# Yusynth_VCA.net
KiCad netlist of a schematic drawn in Altium Designer
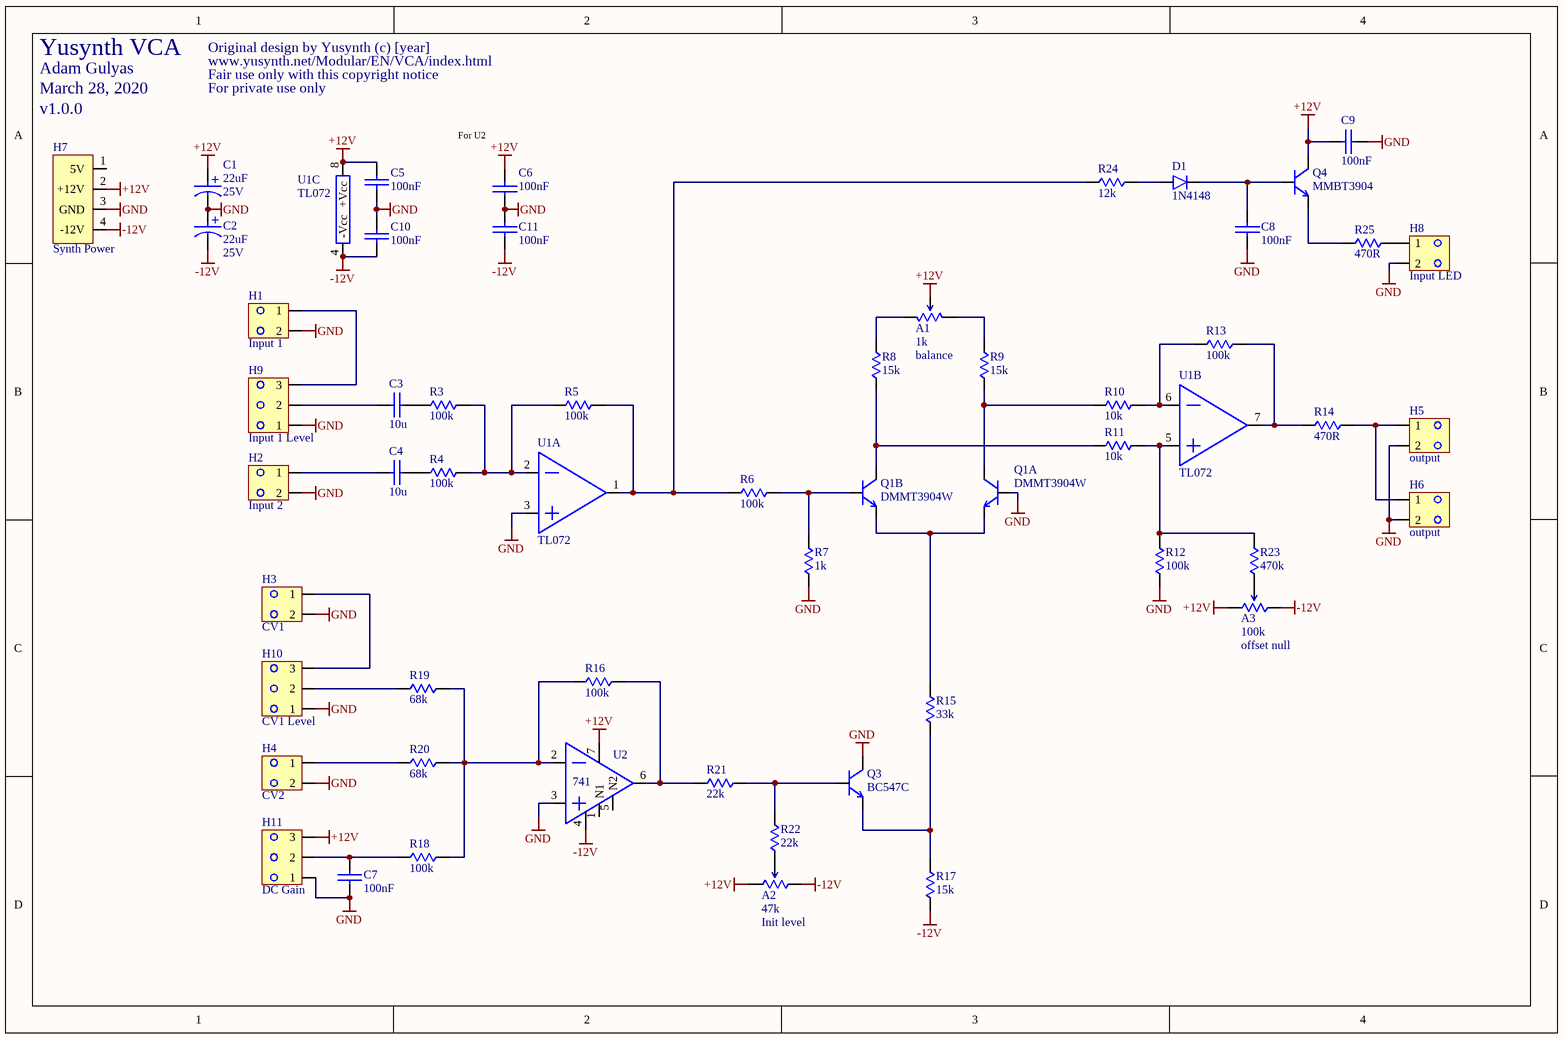
[diagram p0: Yusynth VCA.SchDoc]

(export (version "E")
  (design (tool "Eeschema 10.0.6"))
  (components
    (comp (ref "A1")
      (value "1k")
      (footprint "trim pot")
      (description "trim pot from the random eBay set")
      (fields (field (name "MFG") "Unknown") (field (name "PURPOSE") "balance"))
      (libsource (lib "Adam home") (part "pot - trim - random eBay"))
    )
    (comp (ref "A2")
      (value "47k")
      (footprint "trim pot")
      (description "trim pot from the random eBay set")
      (fields (field (name "MFG") "Unknown") (field (name "PURPOSE") "Init level"))
      (libsource (lib "Adam home") (part "pot - trim - random eBay"))
    )
    (comp (ref "A3")
      (value "100k")
      (footprint "trim pot")
      (description "trim pot from the random eBay set")
      (fields (field (name "MFG") "Unknown") (field (name "PURPOSE") "offset null"))
      (libsource (lib "Adam home") (part "pot - trim - random eBay"))
    )
    (comp (ref "C1")
      (value "22uF")
      (footprint "C - Wurth - SMT - 5mm Dia can")
      (description "CAP 22 UF 20% 25 V")
      (fields
        (field (name "MFG") "Wurth Electronics Inc.")
        (field (name "TOLERANCE") "±20%")
        (field (name "VOLTAGE") "25V")
      )
      (libsource (lib "Adam home") (part "c - 22uF 25V Alum SMT"))
    )
    (comp (ref "C2")
      (value "22uF")
      (footprint "C - Wurth - SMT - 5mm Dia can")
      (description "CAP 22 UF 20% 25 V")
      (fields
        (field (name "MFG") "Wurth Electronics Inc.")
        (field (name "TOLERANCE") "±20%")
        (field (name "VOLTAGE") "25V")
      )
      (libsource (lib "Adam home") (part "c - 22uF 25V Alum SMT"))
    )
    (comp (ref "C3")
      (value "10u")
      (footprint "JEDEC - 0805")
      (description "CAP CER 10UF 35V X5R 0805")
      (fields (field (name "MFG") "Murata") (field (name "VOLTAGE") "35V"))
      (libsource (lib "Adam home") (part "c - 10uF 35V 0805"))
    )
    (comp (ref "C4")
      (value "10u")
      (footprint "JEDEC - 0805")
      (description "CAP CER 10UF 35V X5R 0805")
      (fields (field (name "MFG") "Murata") (field (name "VOLTAGE") "35V"))
      (libsource (lib "Adam home") (part "c - 10uF 35V 0805"))
    )
    (comp (ref "C5")
      (value "100nF")
      (footprint "JEDEC - 0603")
      (description "CAP CER 0.1UF 50V X7R 0603")
      (fields (field (name "MFG") "Yageo") (field (name "VOLTAGE") "50V"))
      (libsource (lib "Adam home") (part "c - 100nF"))
    )
    (comp (ref "C6")
      (value "100nF")
      (footprint "JEDEC - 0603")
      (description "CAP CER 0.1UF 50V X7R 0603")
      (fields (field (name "MFG") "Yageo") (field (name "VOLTAGE") "50V"))
      (libsource (lib "Adam home") (part "c - 100nF"))
    )
    (comp (ref "C7")
      (value "100nF")
      (footprint "JEDEC - 0603")
      (description "CAP CER 0.1UF 50V X7R 0603")
      (fields (field (name "MFG") "Yageo") (field (name "VOLTAGE") "50V"))
      (libsource (lib "Adam home") (part "c - 100nF"))
    )
    (comp (ref "C8")
      (value "100nF")
      (footprint "JEDEC - 0603")
      (description "CAP CER 0.1UF 50V X7R 0603")
      (fields (field (name "MFG") "Yageo") (field (name "VOLTAGE") "50V"))
      (libsource (lib "Adam home") (part "c - 100nF"))
    )
    (comp (ref "C9")
      (value "100nF")
      (footprint "JEDEC - 0603")
      (description "CAP CER 0.1UF 50V X7R 0603")
      (fields (field (name "MFG") "Yageo") (field (name "VOLTAGE") "50V"))
      (libsource (lib "Adam home") (part "c - 100nF"))
    )
    (comp (ref "C10")
      (value "100nF")
      (footprint "JEDEC - 0603")
      (description "CAP CER 0.1UF 50V X7R 0603")
      (fields (field (name "MFG") "Yageo") (field (name "VOLTAGE") "50V"))
      (libsource (lib "Adam home") (part "c - 100nF"))
    )
    (comp (ref "C11")
      (value "100nF")
      (footprint "JEDEC - 0603")
      (description "CAP CER 0.1UF 50V X7R 0603")
      (fields (field (name "MFG") "Yageo") (field (name "VOLTAGE") "50V"))
      (libsource (lib "Adam home") (part "c - 100nF"))
    )
    (comp (ref "D1")
      (value "1N4148")
      (footprint "SOD 123")
      (description "DIODE GEN PURP 75V 250MA SOD123")
      (fields (field (name "MFG") "SMC Diode Solutions"))
      (libsource (lib "Adam home") (part "Diode - 1N4148 - SOD123"))
    )
    (comp (ref "H1")
      (value "1x2 TH Male")
      (footprint "H - KK 100 - TH - 1x2")
      (description "CONN HEADER 2POS .100 VERT TIN")
      (fields (field (name "MFG") "Molex") (field (name "PURPOSE") "Input 1"))
      (libsource (lib "") (part "Header - KK 6373 - 1x2_1"))
    )
    (comp (ref "H2")
      (value "1x2 TH Male")
      (footprint "H - KK 100 - TH - 1x2")
      (description "CONN HEADER 2POS .100 VERT TIN")
      (fields (field (name "MFG") "Molex") (field (name "PURPOSE") "Input 2"))
      (libsource (lib "") (part "Header - KK 6373 - 1x2_1"))
    )
    (comp (ref "H3")
      (value "1x2 TH Male")
      (footprint "H - KK 100 - TH - 1x2")
      (description "CONN HEADER 2POS .100 VERT TIN")
      (fields (field (name "MFG") "Molex") (field (name "PURPOSE") "CV1"))
      (libsource (lib "") (part "Header - KK 6373 - 1x2_1"))
    )
    (comp (ref "H4")
      (value "1x2 TH Male")
      (footprint "H - KK 100 - TH - 1x2")
      (description "CONN HEADER 2POS .100 VERT TIN")
      (fields (field (name "MFG") "Molex") (field (name "PURPOSE") "CV2"))
      (libsource (lib "") (part "Header - KK 6373 - 1x2_1"))
    )
    (comp (ref "H5")
      (value "1x2 TH Male")
      (footprint "H - KK 100 - TH - 1x2")
      (description "CONN HEADER 2POS .100 VERT TIN")
      (fields (field (name "MFG") "Molex") (field (name "PURPOSE") "output"))
      (libsource (lib "Adam home") (part "Header - KK 6373 - 1x2"))
    )
    (comp (ref "H6")
      (value "1x2 TH Male")
      (footprint "H - KK 100 - TH - 1x2")
      (description "CONN HEADER 2POS .100 VERT TIN")
      (fields (field (name "MFG") "Molex") (field (name "PURPOSE") "output"))
      (libsource (lib "Adam home") (part "Header - KK 6373 - 1x2"))
    )
    (comp (ref "H7")
      (value "Synth Power")
      (footprint "Power Connector 3")
      (description "CONN HEADER EH SIDE 6POS 2.5MM")
      (fields (field (name "MFG") "S6B-EH(LF)(SN)"))
      (libsource (lib "Synth UI") (part "h - Power - 1x4"))
    )
    (comp (ref "H8")
      (value "1x2 TH Male")
      (footprint "H - KK 100 - TH - 1x2")
      (description "CONN HEADER 2POS .100 VERT TIN")
      (fields (field (name "MFG") "Molex") (field (name "PURPOSE") "Input LED"))
      (libsource (lib "Adam home") (part "Header - KK 6373 - 1x2"))
    )
    (comp (ref "H9")
      (value "1x3 TH Male")
      (footprint "H - KK 100 - TH - 1x3")
      (description "CONN HEADER 3POS .100 VERT TIN")
      (fields (field (name "MFG") "Molex") (field (name "PURPOSE") "Input 1 Level"))
      (libsource (lib "Adam home") (part "Header - KK 6373 - 1x3"))
    )
    (comp (ref "H10")
      (value "1x3 TH Male")
      (footprint "H - KK 100 - TH - 1x3")
      (description "CONN HEADER 3POS .100 VERT TIN")
      (fields (field (name "MFG") "Molex") (field (name "PURPOSE") "CV1 Level"))
      (libsource (lib "Adam home") (part "Header - KK 6373 - 1x3"))
    )
    (comp (ref "H11")
      (value "1x3 TH Male")
      (footprint "H - KK 100 - TH - 1x3")
      (description "CONN HEADER 3POS .100 VERT TIN")
      (fields (field (name "MFG") "Molex") (field (name "PURPOSE") "DC Gain"))
      (libsource (lib "Adam home") (part "Header - KK 6373 - 1x3"))
    )
    (comp (ref "Q1")
      (value "DMMT3904W")
      (footprint "Diodes Inc - SOT363")
      (description "TRANS 2NPN 40V 0.2A SOT363")
      (fields (field (name "MFG") "Diodes Inc."))
      (libsource (lib "Adam home") (part "tran - matched npn - DMMT3904W"))
    )
    (comp (ref "Q3")
      (value "BC547C")
      (footprint "TO 92 - ON Semi")
      (description "TRANS NPN 45V 0.1A TO-92")
      (fields (field (name "MFG") "ON Semi"))
      (libsource (lib "Adam home") (part "t - BJT - npn - BC547C"))
    )
    (comp (ref "Q4")
      (value "MMBT3904")
      (footprint "SOT 23")
      (description "TRANS NPN 40V 0.2A SOT23")
      (fields (field (name "MFG") "ON Semi"))
      (libsource (lib "Adam home") (part "t - BJT - npn - MMBT3904"))
    )
    (comp (ref "R3")
      (value "100k")
      (footprint "JEDEC - 0603")
      (description "RES SMD 100K OHM 5% 1/10W 0603")
      (fields (field (name "MFG") "Yageo") (field (name "POWER") "0.1W"))
      (libsource (lib "stock R") (part "5 - 100K 5% 0603"))
    )
    (comp (ref "R4")
      (value "100k")
      (footprint "JEDEC - 0603")
      (description "RES SMD 100K OHM 5% 1/10W 0603")
      (fields (field (name "MFG") "Yageo") (field (name "POWER") "0.1W"))
      (libsource (lib "stock R") (part "5 - 100K 5% 0603"))
    )
    (comp (ref "R5")
      (value "100k")
      (footprint "JEDEC - 0603")
      (description "RES SMD 100K OHM 5% 1/10W 0603")
      (fields (field (name "MFG") "Yageo") (field (name "POWER") "0.1W"))
      (libsource (lib "stock R") (part "5 - 100K 5% 0603"))
    )
    (comp (ref "R6")
      (value "100k")
      (footprint "JEDEC - 0603")
      (description "RES SMD 100K OHM 5% 1/10W 0603")
      (fields (field (name "MFG") "Yageo") (field (name "POWER") "0.1W"))
      (libsource (lib "stock R") (part "5 - 100K 5% 0603"))
    )
    (comp (ref "R7")
      (value "1k")
      (footprint "JEDEC - 0603")
      (description "RES SMD 1K OHM 5% 1/10W 0603")
      (fields (field (name "MFG") "Yageo") (field (name "POWER") "0.1W"))
      (libsource (lib "stock R") (part "3 - 1.0K 5% 0603"))
    )
    (comp (ref "R8")
      (value "15k")
      (footprint "JEDEC - 0603")
      (description "RES SMD 15K OHM 5% 1/10W 0603")
      (fields (field (name "MFG") "Yageo") (field (name "POWER") "0.1W"))
      (libsource (lib "stock R") (part "4 - 15K 5% 0603"))
    )
    (comp (ref "R9")
      (value "15k")
      (footprint "JEDEC - 0603")
      (description "RES SMD 15K OHM 5% 1/10W 0603")
      (fields (field (name "MFG") "Yageo") (field (name "POWER") "0.1W"))
      (libsource (lib "stock R") (part "4 - 15K 5% 0603"))
    )
    (comp (ref "R10")
      (value "10k")
      (footprint "JEDEC - 0603")
      (description "RES SMD 10K OHM 5% 1/10W 0603")
      (fields (field (name "MFG") "Yageo") (field (name "POWER") "0.1W"))
      (libsource (lib "stock R") (part "4 - 10K 5% 0603"))
    )
    (comp (ref "R11")
      (value "10k")
      (footprint "JEDEC - 0603")
      (description "RES SMD 10K OHM 5% 1/10W 0603")
      (fields (field (name "MFG") "Yageo") (field (name "POWER") "0.1W"))
      (libsource (lib "stock R") (part "4 - 10K 5% 0603"))
    )
    (comp (ref "R12")
      (value "100k")
      (footprint "JEDEC - 0603")
      (description "RES SMD 100K OHM 5% 1/10W 0603")
      (fields (field (name "MFG") "Yageo") (field (name "POWER") "0.1W"))
      (libsource (lib "stock R") (part "5 - 100K 5% 0603"))
    )
    (comp (ref "R13")
      (value "100k")
      (footprint "JEDEC - 0603")
      (description "RES SMD 100K OHM 5% 1/10W 0603")
      (fields (field (name "MFG") "Yageo") (field (name "POWER") "0.1W"))
      (libsource (lib "stock R") (part "5 - 100K 5% 0603"))
    )
    (comp (ref "R14")
      (value "470R")
      (footprint "JEDEC - 0603")
      (description "RES SMD 470 OHM 5% 1/10W 0603")
      (fields (field (name "MFG") "Yageo") (field (name "POWER") "0.1W"))
      (libsource (lib "stock R") (part "2 - 470R 5% 0603"))
    )
    (comp (ref "R15")
      (value "33k")
      (footprint "JEDEC - 0603")
      (description "RES SMD 33K OHM 5% 1/10W 0603")
      (fields (field (name "MFG") "Yageo") (field (name "POWER") "0.1W"))
      (libsource (lib "stock R") (part "4 - 33K 5% 0603"))
    )
    (comp (ref "R16")
      (value "100k")
      (footprint "JEDEC - 0603")
      (description "RES SMD 100K OHM 5% 1/10W 0603")
      (fields (field (name "MFG") "Yageo") (field (name "POWER") "0.1W"))
      (libsource (lib "stock R") (part "5 - 100K 5% 0603"))
    )
    (comp (ref "R17")
      (value "15k")
      (footprint "JEDEC - 0603")
      (description "RES SMD 15K OHM 5% 1/10W 0603")
      (fields (field (name "MFG") "Yageo") (field (name "POWER") "0.1W"))
      (libsource (lib "stock R") (part "4 - 15K 5% 0603"))
    )
    (comp (ref "R18")
      (value "100k")
      (footprint "JEDEC - 0603")
      (description "RES SMD 100K OHM 5% 1/10W 0603")
      (fields (field (name "MFG") "Yageo") (field (name "POWER") "0.1W"))
      (libsource (lib "stock R") (part "5 - 100K 5% 0603"))
    )
    (comp (ref "R19")
      (value "68k")
      (footprint "JEDEC - 0603")
      (description "RES SMD 68K OHM 5% 1/10W 0603")
      (fields (field (name "MFG") "Yageo") (field (name "POWER") "0.1W"))
      (libsource (lib "stock R") (part "4 - 68K 5% 0603"))
    )
    (comp (ref "R20")
      (value "68k")
      (footprint "JEDEC - 0603")
      (description "RES SMD 68K OHM 5% 1/10W 0603")
      (fields (field (name "MFG") "Yageo") (field (name "POWER") "0.1W"))
      (libsource (lib "stock R") (part "4 - 68K 5% 0603"))
    )
    (comp (ref "R21")
      (value "22k")
      (footprint "JEDEC - 0603")
      (description "RES SMD 22K OHM 5% 1/10W 0603")
      (fields (field (name "MFG") "Yageo") (field (name "POWER") "0.1W"))
      (libsource (lib "stock R") (part "4 - 22K 5% 0603"))
    )
    (comp (ref "R22")
      (value "22k")
      (footprint "JEDEC - 0603")
      (description "RES SMD 22K OHM 5% 1/10W 0603")
      (fields (field (name "MFG") "Yageo") (field (name "POWER") "0.1W"))
      (libsource (lib "stock R") (part "4 - 22K 5% 0603"))
    )
    (comp (ref "R23")
      (value "470k")
      (footprint "JEDEC - 0603")
      (description "RES SMD 470K OHM 5% 1/10W 0603")
      (fields (field (name "MFG") "Yageo") (field (name "POWER") "0.1W"))
      (libsource (lib "stock R") (part "5 - 470K 5% 0603"))
    )
    (comp (ref "R24")
      (value "12k")
      (footprint "JEDEC - 0603")
      (description "RES SMD 12K OHM 5% 1/10W 0603")
      (fields (field (name "MFG") "Yageo") (field (name "POWER") "0.1W"))
      (libsource (lib "stock R") (part "4 - 12K 5% 0603"))
    )
    (comp (ref "R25")
      (value "470R")
      (footprint "JEDEC - 0603")
      (description "RES SMD 470 OHM 5% 1/10W 0603")
      (fields (field (name "MFG") "Yageo") (field (name "POWER") "0.1W"))
      (libsource (lib "stock R") (part "2 - 470R 5% 0603"))
    )
    (comp (ref "U1")
      (value "TL072")
      (footprint "TI - D (R-PDSO-G8)")
      (description "IC OPAMP JFET 3MHZ 8SOIC")
      (fields (field (name "MFG") "TI"))
      (libsource (lib "Adam home") (part "op amp - TL072"))
    )
    (comp (ref "U2")
      (value "741")
      (footprint "TI - D (R-PDSO-G8)")
      (description "IC OPAMP GP 1MHZ 8SOIC")
      (fields (field (name "MFG") "TI"))
      (libsource (lib "Adam home") (part "op amp - UA741 - TI UA741CDR"))
    )
  )
  (nets
    (net (code "1") (name "+12V") (class "Default")
      (node (ref "A1") (pin "2") (pinfunction "2_2") (pintype "passive"))
      (node (ref "A2") (pin "3") (pinfunction "3_3") (pintype "passive"))
      (node (ref "A3") (pin "3") (pinfunction "3_3") (pintype "passive"))
      (node (ref "C1") (pin "1") (pinfunction "1_1") (pintype "passive"))
      (node (ref "C5") (pin "2") (pintype "passive"))
      (node (ref "C6") (pin "2") (pintype "passive"))
      (node (ref "C9") (pin "1") (pintype "passive"))
      (node (ref "H11") (pin "3") (pinfunction "3_3") (pintype "passive"))
      (node (ref "H7") (pin "2") (pinfunction "+12V_2") (pintype "passive"))
      (node (ref "Q4") (pin "3") (pinfunction "C_3") (pintype "passive"))
      (node (ref "U1") (pin "8") (pinfunction "+Vcc_8") (pintype "passive"))
      (node (ref "U2") (pin "7") (pinfunction "7_7") (pintype "passive"))
    )
    (net (code "2") (name "-12V") (class "Default")
      (node (ref "A2") (pin "1") (pintype "passive"))
      (node (ref "A3") (pin "1") (pintype "passive"))
      (node (ref "C10") (pin "1") (pintype "passive"))
      (node (ref "C11") (pin "1") (pintype "passive"))
      (node (ref "C2") (pin "2") (pinfunction "2_2") (pintype "passive"))
      (node (ref "H7") (pin "4") (pinfunction "-12V_4") (pintype "passive"))
      (node (ref "R17") (pin "1") (pintype "passive"))
      (node (ref "U1") (pin "4") (pinfunction "-Vcc_4") (pintype "passive"))
      (node (ref "U2") (pin "4") (pinfunction "4_4") (pintype "passive"))
    )
    (net (code "3") (name "GND") (class "Default")
      (node (ref "C1") (pin "2") (pinfunction "2_2") (pintype "passive"))
      (node (ref "C10") (pin "2") (pintype "passive"))
      (node (ref "C11") (pin "2") (pintype "passive"))
      (node (ref "C2") (pin "1") (pinfunction "1_1") (pintype "passive"))
      (node (ref "C5") (pin "1") (pintype "passive"))
      (node (ref "C6") (pin "1") (pintype "passive"))
      (node (ref "C7") (pin "1") (pintype "passive"))
      (node (ref "C8") (pin "2") (pintype "passive"))
      (node (ref "C9") (pin "2") (pintype "passive"))
      (node (ref "H1") (pin "2") (pinfunction "2_2") (pintype "passive"))
      (node (ref "H10") (pin "1") (pinfunction "1_1") (pintype "passive"))
      (node (ref "H11") (pin "1") (pinfunction "1_1") (pintype "passive"))
      (node (ref "H2") (pin "2") (pinfunction "2_2") (pintype "passive"))
      (node (ref "H3") (pin "2") (pinfunction "2_2") (pintype "passive"))
      (node (ref "H4") (pin "2") (pinfunction "2_2") (pintype "passive"))
      (node (ref "H5") (pin "2") (pinfunction "2_2") (pintype "passive"))
      (node (ref "H6") (pin "2") (pinfunction "2_2") (pintype "passive"))
      (node (ref "H7") (pin "3") (pinfunction "GND_3") (pintype "passive"))
      (node (ref "H8") (pin "2") (pinfunction "2_2") (pintype "passive"))
      (node (ref "H9") (pin "1") (pinfunction "1_1") (pintype "passive"))
      (node (ref "Q1") (pin "1") (pinfunction "1_1") (pintype "passive"))
      (node (ref "Q3") (pin "1") (pinfunction "C_1") (pintype "passive"))
      (node (ref "R12") (pin "1") (pintype "passive"))
      (node (ref "R7") (pin "1") (pintype "passive"))
      (node (ref "U1") (pin "3") (pinfunction "3_3") (pintype "passive"))
      (node (ref "U2") (pin "3") (pinfunction "3_3") (pintype "passive"))
    )
    (net (code "4") (name "Net-(A1-Pad1)") (class "Default")
      (node (ref "A1") (pin "1") (pintype "passive"))
      (node (ref "R8") (pin "2") (pintype "passive"))
    )
    (net (code "5") (name "Net-(A1-Pad3)") (class "Default")
      (node (ref "A1") (pin "3") (pinfunction "3_3") (pintype "passive"))
      (node (ref "R9") (pin "2") (pintype "passive"))
    )
    (net (code "6") (name "Net-(A2-Pad2)") (class "Default")
      (node (ref "A2") (pin "2") (pinfunction "2_2") (pintype "passive"))
      (node (ref "R22") (pin "1") (pintype "passive"))
    )
    (net (code "7") (name "Net-(A3-Pad2)") (class "Default")
      (node (ref "A3") (pin "2") (pinfunction "2_2") (pintype "passive"))
      (node (ref "R23") (pin "1") (pintype "passive"))
    )
    (net (code "8") (name "Net-(C3-Pad1)") (class "Default")
      (node (ref "C3") (pin "1") (pintype "passive"))
      (node (ref "H9") (pin "2") (pinfunction "2_2") (pintype "passive"))
    )
    (net (code "9") (name "Net-(C3-Pad2)") (class "Default")
      (node (ref "C3") (pin "2") (pintype "passive"))
      (node (ref "R3") (pin "1") (pintype "passive"))
    )
    (net (code "10") (name "Net-(C4-Pad1)") (class "Default")
      (node (ref "C4") (pin "1") (pintype "passive"))
      (node (ref "H2") (pin "1") (pinfunction "1_1") (pintype "passive"))
    )
    (net (code "11") (name "Net-(C4-Pad2)") (class "Default")
      (node (ref "C4") (pin "2") (pintype "passive"))
      (node (ref "R4") (pin "1") (pintype "passive"))
    )
    (net (code "12") (name "Net-(C7-Pad2)") (class "Default")
      (node (ref "C7") (pin "2") (pintype "passive"))
      (node (ref "H11") (pin "2") (pinfunction "2_2") (pintype "passive"))
      (node (ref "R18") (pin "1") (pintype "passive"))
    )
    (net (code "13") (name "Net-(D1-Pad1)") (class "Default")
      (node (ref "D1") (pin "1") (pinfunction "1_1") (pintype "passive"))
      (node (ref "R24") (pin "2") (pintype "passive"))
    )
    (net (code "14") (name "Net-(H1-Pad1)") (class "Default")
      (node (ref "H1") (pin "1") (pinfunction "1_1") (pintype "passive"))
      (node (ref "H9") (pin "3") (pinfunction "3_3") (pintype "passive"))
    )
    (net (code "15") (name "Net-(H4-Pad1)") (class "Default")
      (node (ref "H4") (pin "1") (pinfunction "1_1") (pintype "passive"))
      (node (ref "R20") (pin "1") (pintype "passive"))
    )
    (net (code "16") (name "Net-(H5-Pad1)") (class "Default")
      (node (ref "H5") (pin "1") (pinfunction "1_1") (pintype "passive"))
      (node (ref "H6") (pin "1") (pinfunction "1_1") (pintype "passive"))
      (node (ref "R14") (pin "2") (pintype "passive"))
    )
    (net (code "17") (name "Net-(H8-Pad1)") (class "Default")
      (node (ref "H8") (pin "1") (pinfunction "1_1") (pintype "passive"))
      (node (ref "R25") (pin "2") (pintype "passive"))
    )
    (net (code "18") (name "Net-(H10-Pad2)") (class "Default")
      (node (ref "H10") (pin "2") (pinfunction "2_2") (pintype "passive"))
      (node (ref "R19") (pin "1") (pintype "passive"))
    )
    (net (code "19") (name "Net-(H10-Pad3)") (class "Default")
      (node (ref "H10") (pin "3") (pinfunction "3_3") (pintype "passive"))
      (node (ref "H3") (pin "1") (pinfunction "1_1") (pintype "passive"))
    )
    (net (code "20") (name "Net-(Q1-Pad2)") (class "Default")
      (node (ref "Q1") (pin "2") (pinfunction "2_2") (pintype "passive"))
      (node (ref "R6") (pin "2") (pintype "passive"))
      (node (ref "R7") (pin "2") (pintype "passive"))
    )
    (net (code "21") (name "Net-(Q1-Pad3)") (class "Default")
      (node (ref "Q1") (pin "3") (pinfunction "3_3") (pintype "passive"))
      (node (ref "R11") (pin "1") (pintype "passive"))
      (node (ref "R8") (pin "1") (pintype "passive"))
    )
    (net (code "22") (name "Net-(Q1-Pad4)") (class "Default")
      (node (ref "Q1") (pin "4") (pinfunction "4_4") (pintype "passive"))
      (node (ref "Q1") (pin "5") (pinfunction "5_5") (pintype "passive"))
      (node (ref "R15") (pin "2") (pintype "passive"))
    )
    (net (code "23") (name "Net-(Q1-Pad6)") (class "Default")
      (node (ref "Q1") (pin "6") (pinfunction "6_6") (pintype "passive"))
      (node (ref "R10") (pin "1") (pintype "passive"))
      (node (ref "R9") (pin "1") (pintype "passive"))
    )
    (net (code "24") (name "Net-(Q3-B)") (class "Default")
      (node (ref "Q3") (pin "2") (pinfunction "B_2") (pintype "passive"))
      (node (ref "R21") (pin "2") (pintype "passive"))
      (node (ref "R22") (pin "2") (pintype "passive"))
    )
    (net (code "25") (name "Net-(Q3-E)") (class "Default")
      (node (ref "Q3") (pin "3") (pinfunction "E_3") (pintype "passive"))
      (node (ref "R15") (pin "1") (pintype "passive"))
      (node (ref "R17") (pin "2") (pintype "passive"))
    )
    (net (code "26") (name "Net-(Q4-B)") (class "Default")
      (node (ref "C8") (pin "1") (pintype "passive"))
      (node (ref "D1") (pin "2") (pinfunction "2_2") (pintype "passive"))
      (node (ref "Q4") (pin "1") (pinfunction "B_1") (pintype "passive"))
    )
    (net (code "27") (name "Net-(Q4-E)") (class "Default")
      (node (ref "Q4") (pin "2") (pinfunction "E_2") (pintype "passive"))
      (node (ref "R25") (pin "1") (pintype "passive"))
    )
    (net (code "28") (name "Net-(R3-Pad2)") (class "Default")
      (node (ref "R3") (pin "2") (pintype "passive"))
      (node (ref "R4") (pin "2") (pintype "passive"))
      (node (ref "R5") (pin "1") (pintype "passive"))
      (node (ref "U1") (pin "2") (pinfunction "2_2") (pintype "passive"))
    )
    (net (code "29") (name "Net-(R10-Pad2)") (class "Default")
      (node (ref "R10") (pin "2") (pintype "passive"))
      (node (ref "R13") (pin "1") (pintype "passive"))
      (node (ref "U1") (pin "6") (pinfunction "6_6") (pintype "passive"))
    )
    (net (code "30") (name "Net-(R11-Pad2)") (class "Default")
      (node (ref "R11") (pin "2") (pintype "passive"))
      (node (ref "R12") (pin "2") (pintype "passive"))
      (node (ref "R23") (pin "2") (pintype "passive"))
      (node (ref "U1") (pin "5") (pinfunction "5_5") (pintype "passive"))
    )
    (net (code "31") (name "Net-(R13-Pad2)") (class "Default")
      (node (ref "R13") (pin "2") (pintype "passive"))
      (node (ref "R14") (pin "1") (pintype "passive"))
      (node (ref "U1") (pin "7") (pinfunction "7_7") (pintype "passive"))
    )
    (net (code "32") (name "Net-(R16-Pad1)") (class "Default")
      (node (ref "R16") (pin "1") (pintype "passive"))
      (node (ref "R18") (pin "2") (pintype "passive"))
      (node (ref "R19") (pin "2") (pintype "passive"))
      (node (ref "R20") (pin "2") (pintype "passive"))
      (node (ref "U2") (pin "2") (pinfunction "2_2") (pintype "passive"))
    )
    (net (code "33") (name "Net-(R16-Pad2)") (class "Default")
      (node (ref "R16") (pin "2") (pintype "passive"))
      (node (ref "R21") (pin "1") (pintype "passive"))
      (node (ref "U2") (pin "6") (pinfunction "6_6") (pintype "passive"))
    )
    (net (code "34") (name "Net-(R24-Pad1)") (class "Default")
      (node (ref "R24") (pin "1") (pintype "passive"))
      (node (ref "R5") (pin "2") (pintype "passive"))
      (node (ref "R6") (pin "1") (pintype "passive"))
      (node (ref "U1") (pin "1") (pinfunction "1_1") (pintype "passive"))
    )
    (net (code "35") (name "unconnected-(H7-5V-Pad1)") (class "Default")
      (node (ref "H7") (pin "1") (pinfunction "5V_1") (pintype "passive"))
    )
    (net (code "36") (name "unconnected-(U2-N1-Pad1)") (class "Default")
      (node (ref "U2") (pin "1") (pinfunction "N1_1") (pintype "passive"))
    )
    (net (code "37") (name "unconnected-(U2-N2-Pad5)") (class "Default")
      (node (ref "U2") (pin "5") (pinfunction "N2_5") (pintype "passive"))
    )
  )
)
